# lw-skit.net
KiCad netlist of a schematic drawn in Altium Designer
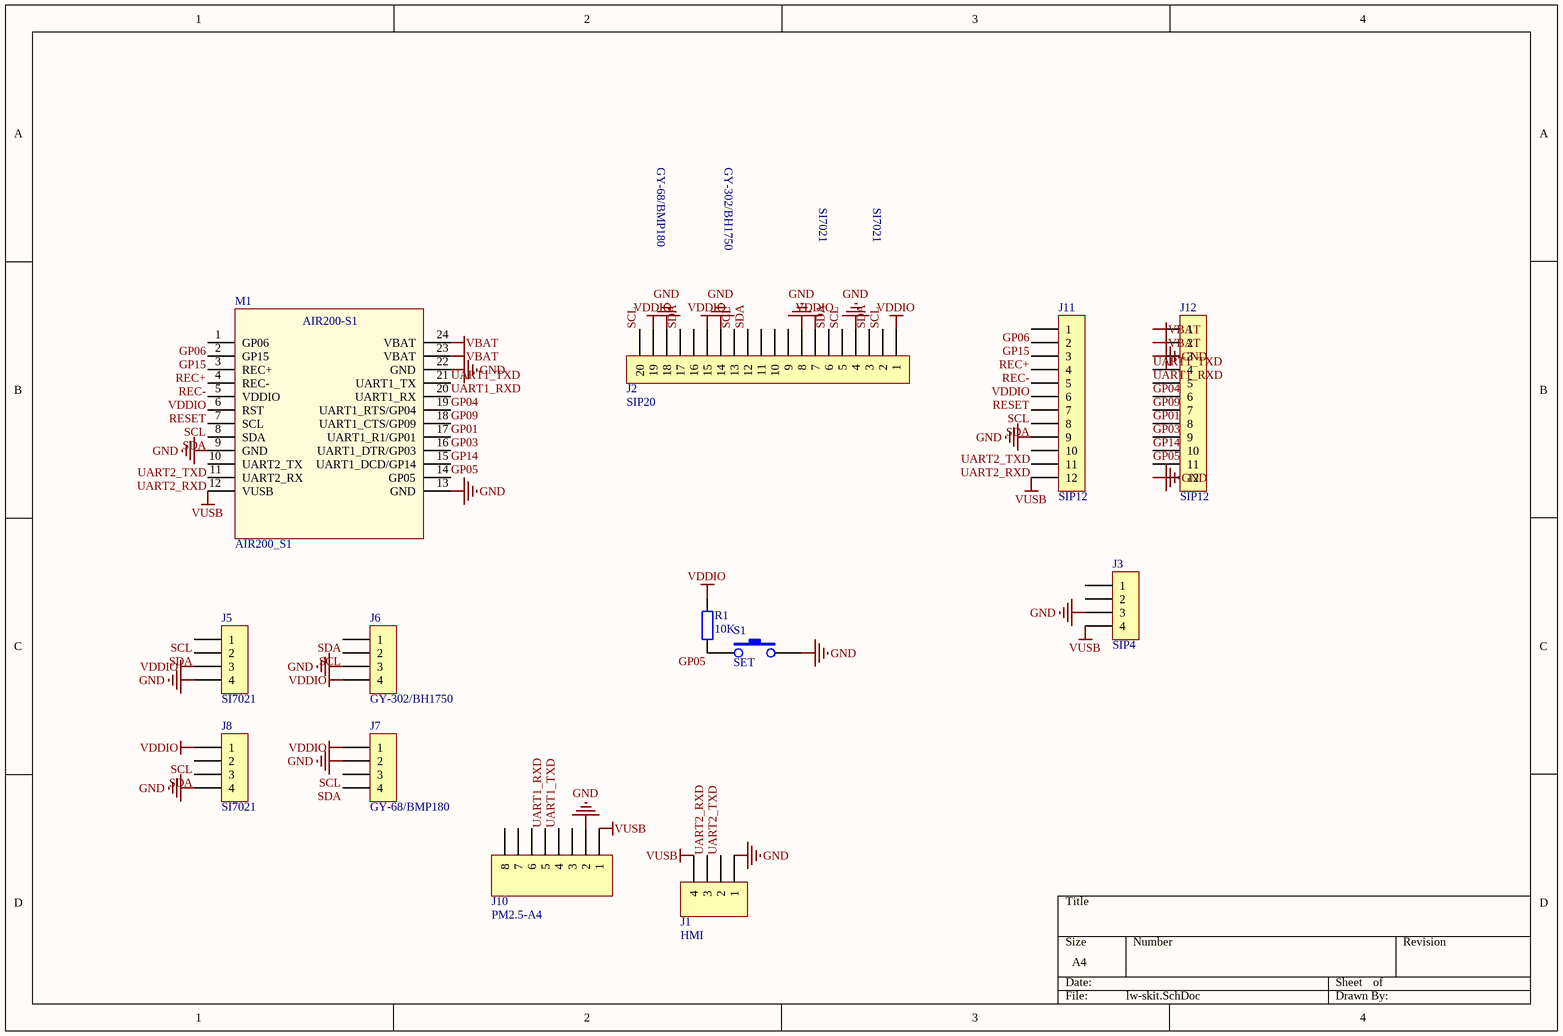
[diagram p0: lw-skit.SchDoc]

(export (version "E")
  (design (tool "Eeschema 10.0.6"))
  (components
    (comp (ref "J1")
      (value "HMI")
      (footprint "XH2.54_4P")
      (description "XH2.54-4P")
      (libsource (lib "wyf") (part "XH2.54-4P"))
    )
    (comp (ref "J2") (value "SIP20") (footprint "DB-1X20") (libsource (lib "wyf") (part "SIP20")))
    (comp (ref "J3") (value "SIP4") (footprint "DB-1X4") (libsource (lib "wyf") (part "SIP4")))
    (comp (ref "J5") (value "SI7021") (footprint "DB-1X4") (libsource (lib "wyf") (part "SIP4")))
    (comp (ref "J6") (value "GY-302/BH1750") (footprint "DB-1X4") (libsource (lib "wyf") (part "SIP4")))
    (comp (ref "J7") (value "GY-68/BMP180") (footprint "DB-1X4") (libsource (lib "wyf") (part "SIP4")))
    (comp (ref "J8") (value "SI7021") (footprint "DB-1X4") (libsource (lib "wyf") (part "SIP4")))
    (comp (ref "J10")
      (value "PM2.5-A4")
      (footprint "1.27*8")
      (description "FPC-1.27-8P")
      (libsource (lib "wyf") (part "FPC-1.27-8P"))
    )
    (comp (ref "J11") (value "SIP12") (footprint "DB-1X12") (libsource (lib "wyf") (part "SIP12")))
    (comp (ref "J12") (value "SIP12") (footprint "DB-1X12") (libsource (lib "wyf") (part "SIP12")))
    (comp (ref "M1") (value "AIR200_S1") (footprint "AIR200-S1") (libsource (lib "wyf") (part "AIR200_S1")))
    (comp (ref "R1")
      (value "10K")
      (footprint "RES-SMD-0603")
      (description "Res0603")
      (libsource (lib "wyf") (part "Res0603"))
    )
    (comp (ref "S1")
      (value "SET")
      (footprint "upkey")
      (description "按键开关立式")
      (libsource (lib "wyf") (part "SW_KEY_L"))
    )
  )
  (nets
    (net (code "1") (name "/GP01") (class "Default")
      (node (ref "J12") (pin "8") (pinfunction "8_8") (pintype "passive"))
      (node (ref "M1") (pin "17") (pinfunction "UART1_R1/GP01_17") (pintype "passive"))
    )
    (net (code "2") (name "/GP03") (class "Default")
      (node (ref "J12") (pin "9") (pinfunction "9_9") (pintype "passive"))
      (node (ref "M1") (pin "16") (pinfunction "UART1_DTR/GP03_16") (pintype "passive"))
    )
    (net (code "3") (name "/GP04") (class "Default")
      (node (ref "J12") (pin "6") (pinfunction "6_6") (pintype "passive"))
      (node (ref "M1") (pin "19") (pinfunction "UART1_RTS/GP04_19") (pintype "passive"))
    )
    (net (code "4") (name "/GP05") (class "Default")
      (node (ref "J12") (pin "11") (pinfunction "11_11") (pintype "passive"))
      (node (ref "M1") (pin "14") (pinfunction "GP05_14") (pintype "passive"))
      (node (ref "R1") (pin "1") (pinfunction "0_1") (pintype "passive"))
      (node (ref "S1") (pin "1") (pinfunction "1_1") (pintype "passive"))
    )
    (net (code "5") (name "/GP06") (class "Default")
      (node (ref "J11") (pin "1") (pinfunction "1_1") (pintype "passive"))
      (node (ref "M1") (pin "1") (pinfunction "GP06_1") (pintype "passive"))
    )
    (net (code "6") (name "/GP09") (class "Default")
      (node (ref "J12") (pin "7") (pinfunction "7_7") (pintype "passive"))
      (node (ref "M1") (pin "18") (pinfunction "UART1_CTS/GP09_18") (pintype "passive"))
    )
    (net (code "7") (name "/GP14") (class "Default")
      (node (ref "J12") (pin "10") (pinfunction "10_10") (pintype "passive"))
      (node (ref "M1") (pin "15") (pinfunction "UART1_DCD/GP14_15") (pintype "passive"))
    )
    (net (code "8") (name "/GP15") (class "Default")
      (node (ref "J11") (pin "2") (pinfunction "2_2") (pintype "passive"))
      (node (ref "M1") (pin "2") (pinfunction "GP15_2") (pintype "passive"))
    )
    (net (code "9") (name "/REC+") (class "Default")
      (node (ref "J11") (pin "3") (pinfunction "3_3") (pintype "passive"))
      (node (ref "M1") (pin "3") (pinfunction "REC+_3") (pintype "passive"))
    )
    (net (code "10") (name "/REC-") (class "Default")
      (node (ref "J11") (pin "4") (pinfunction "4_4") (pintype "passive"))
      (node (ref "M1") (pin "4") (pinfunction "REC-_4") (pintype "passive"))
    )
    (net (code "11") (name "/RESET") (class "Default")
      (node (ref "J11") (pin "6") (pinfunction "6_6") (pintype "passive"))
      (node (ref "M1") (pin "6") (pinfunction "RST_6") (pintype "passive"))
    )
    (net (code "12") (name "/SCL") (class "Default")
      (node (ref "J11") (pin "7") (pinfunction "7_7") (pintype "passive"))
      (node (ref "J2") (pin "13") (pinfunction "13_13") (pintype "passive"))
      (node (ref "J2") (pin "2") (pinfunction "2_2") (pintype "passive"))
      (node (ref "J2") (pin "20") (pinfunction "20_20") (pintype "passive"))
      (node (ref "J2") (pin "5") (pinfunction "5_5") (pintype "passive"))
      (node (ref "J5") (pin "1") (pinfunction "1_1") (pintype "passive"))
      (node (ref "J6") (pin "2") (pinfunction "2_2") (pintype "passive"))
      (node (ref "J7") (pin "3") (pinfunction "3_3") (pintype "passive"))
      (node (ref "J8") (pin "2") (pinfunction "2_2") (pintype "passive"))
      (node (ref "M1") (pin "7") (pinfunction "SCL_7") (pintype "passive"))
    )
    (net (code "13") (name "/SDA") (class "Default")
      (node (ref "J11") (pin "8") (pinfunction "8_8") (pintype "passive"))
      (node (ref "J2") (pin "12") (pinfunction "12_12") (pintype "passive"))
      (node (ref "J2") (pin "17") (pinfunction "17_17") (pintype "passive"))
      (node (ref "J2") (pin "3") (pinfunction "3_3") (pintype "passive"))
      (node (ref "J2") (pin "6") (pinfunction "6_6") (pintype "passive"))
      (node (ref "J5") (pin "2") (pinfunction "2_2") (pintype "passive"))
      (node (ref "J6") (pin "1") (pinfunction "1_1") (pintype "passive"))
      (node (ref "J7") (pin "4") (pinfunction "4_4") (pintype "passive"))
      (node (ref "J8") (pin "3") (pinfunction "3_3") (pintype "passive"))
      (node (ref "M1") (pin "8") (pinfunction "SDA_8") (pintype "passive"))
    )
    (net (code "14") (name "/UART1_RXD") (class "Default")
      (node (ref "J10") (pin "5") (pinfunction "5_5") (pintype "passive"))
      (node (ref "J12") (pin "5") (pinfunction "5_5") (pintype "passive"))
      (node (ref "M1") (pin "20") (pinfunction "UART1_RX_20") (pintype "passive"))
    )
    (net (code "15") (name "/UART1_TXD") (class "Default")
      (node (ref "J10") (pin "4") (pinfunction "4_4") (pintype "passive"))
      (node (ref "J12") (pin "4") (pinfunction "4_4") (pintype "passive"))
      (node (ref "M1") (pin "21") (pinfunction "UART1_TX_21") (pintype "passive"))
    )
    (net (code "16") (name "/UART2_RXD") (class "Default")
      (node (ref "J1") (pin "3") (pinfunction "3_3") (pintype "passive"))
      (node (ref "J11") (pin "11") (pinfunction "11_11") (pintype "passive"))
      (node (ref "M1") (pin "11") (pinfunction "UART2_RX_11") (pintype "passive"))
    )
    (net (code "17") (name "/UART2_TXD") (class "Default")
      (node (ref "J1") (pin "2") (pinfunction "2_2") (pintype "passive"))
      (node (ref "J11") (pin "10") (pinfunction "10_10") (pintype "passive"))
      (node (ref "M1") (pin "10") (pinfunction "UART2_TX_10") (pintype "passive"))
    )
    (net (code "18") (name "GND") (class "Default")
      (node (ref "J1") (pin "1") (pinfunction "1_1") (pintype "passive"))
      (node (ref "J10") (pin "2") (pinfunction "2_2") (pintype "passive"))
      (node (ref "J11") (pin "9") (pinfunction "9_9") (pintype "passive"))
      (node (ref "J12") (pin "12") (pinfunction "12_12") (pintype "passive"))
      (node (ref "J12") (pin "3") (pinfunction "3_3") (pintype "passive"))
      (node (ref "J2") (pin "14") (pinfunction "14_14") (pintype "passive"))
      (node (ref "J2") (pin "18") (pinfunction "18_18") (pintype "passive"))
      (node (ref "J2") (pin "4") (pinfunction "4_4") (pintype "passive"))
      (node (ref "J2") (pin "8") (pinfunction "8_8") (pintype "passive"))
      (node (ref "J3") (pin "3") (pinfunction "3_3") (pintype "passive"))
      (node (ref "J5") (pin "4") (pinfunction "4_4") (pintype "passive"))
      (node (ref "J6") (pin "3") (pinfunction "3_3") (pintype "passive"))
      (node (ref "J7") (pin "2") (pinfunction "2_2") (pintype "passive"))
      (node (ref "J8") (pin "4") (pinfunction "4_4") (pintype "passive"))
      (node (ref "M1") (pin "13") (pinfunction "GND_13") (pintype "passive"))
      (node (ref "M1") (pin "22") (pinfunction "GND_22") (pintype "passive"))
      (node (ref "M1") (pin "9") (pinfunction "GND_9") (pintype "passive"))
      (node (ref "S1") (pin "2") (pinfunction "2_2") (pintype "passive"))
    )
    (net (code "19") (name "VBAT") (class "Default")
      (node (ref "J12") (pin "1") (pinfunction "1_1") (pintype "passive"))
      (node (ref "J12") (pin "2") (pinfunction "2_2") (pintype "passive"))
      (node (ref "M1") (pin "23") (pinfunction "VBAT_23") (pintype "passive"))
      (node (ref "M1") (pin "24") (pinfunction "VBAT_24") (pintype "passive"))
    )
    (net (code "20") (name "VDDIO") (class "Default")
      (node (ref "J11") (pin "5") (pinfunction "5_5") (pintype "passive"))
      (node (ref "J2") (pin "1") (pinfunction "1_1") (pintype "passive"))
      (node (ref "J2") (pin "15") (pinfunction "15_15") (pintype "passive"))
      (node (ref "J2") (pin "19") (pinfunction "19_19") (pintype "passive"))
      (node (ref "J2") (pin "7") (pinfunction "7_7") (pintype "passive"))
      (node (ref "J5") (pin "3") (pinfunction "3_3") (pintype "passive"))
      (node (ref "J6") (pin "4") (pinfunction "4_4") (pintype "passive"))
      (node (ref "J7") (pin "1") (pinfunction "1_1") (pintype "passive"))
      (node (ref "J8") (pin "1") (pinfunction "1_1") (pintype "passive"))
      (node (ref "M1") (pin "5") (pinfunction "VDDIO_5") (pintype "passive"))
      (node (ref "R1") (pin "2") (pinfunction "1_2") (pintype "passive"))
    )
    (net (code "21") (name "VUSB") (class "Default")
      (node (ref "J1") (pin "4") (pinfunction "4_4") (pintype "passive"))
      (node (ref "J10") (pin "1") (pinfunction "1_1") (pintype "passive"))
      (node (ref "J11") (pin "12") (pinfunction "12_12") (pintype "passive"))
      (node (ref "J3") (pin "4") (pinfunction "4_4") (pintype "passive"))
      (node (ref "M1") (pin "12") (pinfunction "VUSB_12") (pintype "passive"))
    )
    (net (code "22") (name "unconnected-(J2-Pad9)") (class "Default")
      (node (ref "J2") (pin "9") (pinfunction "9_9") (pintype "passive"))
    )
    (net (code "23") (name "unconnected-(J2-Pad10)") (class "Default")
      (node (ref "J2") (pin "10") (pinfunction "10_10") (pintype "passive"))
    )
    (net (code "24") (name "unconnected-(J2-Pad11)") (class "Default")
      (node (ref "J2") (pin "11") (pinfunction "11_11") (pintype "passive"))
    )
    (net (code "25") (name "unconnected-(J2-Pad16)") (class "Default")
      (node (ref "J2") (pin "16") (pinfunction "16_16") (pintype "passive"))
    )
    (net (code "26") (name "unconnected-(J3-Pad1)") (class "Default")
      (node (ref "J3") (pin "1") (pinfunction "1_1") (pintype "passive"))
    )
    (net (code "27") (name "unconnected-(J3-Pad2)") (class "Default")
      (node (ref "J3") (pin "2") (pinfunction "2_2") (pintype "passive"))
    )
    (net (code "28") (name "unconnected-(J10-Pad3)") (class "Default")
      (node (ref "J10") (pin "3") (pinfunction "3_3") (pintype "passive"))
    )
    (net (code "29") (name "unconnected-(J10-Pad6)") (class "Default")
      (node (ref "J10") (pin "6") (pinfunction "6_6") (pintype "passive"))
    )
    (net (code "30") (name "unconnected-(J10-Pad7)") (class "Default")
      (node (ref "J10") (pin "7") (pinfunction "7_7") (pintype "passive"))
    )
    (net (code "31") (name "unconnected-(J10-Pad8)") (class "Default")
      (node (ref "J10") (pin "8") (pinfunction "8_8") (pintype "passive"))
    )
  )
)
